# B168B.net
KiCad netlist of a schematic drawn in EAGLE
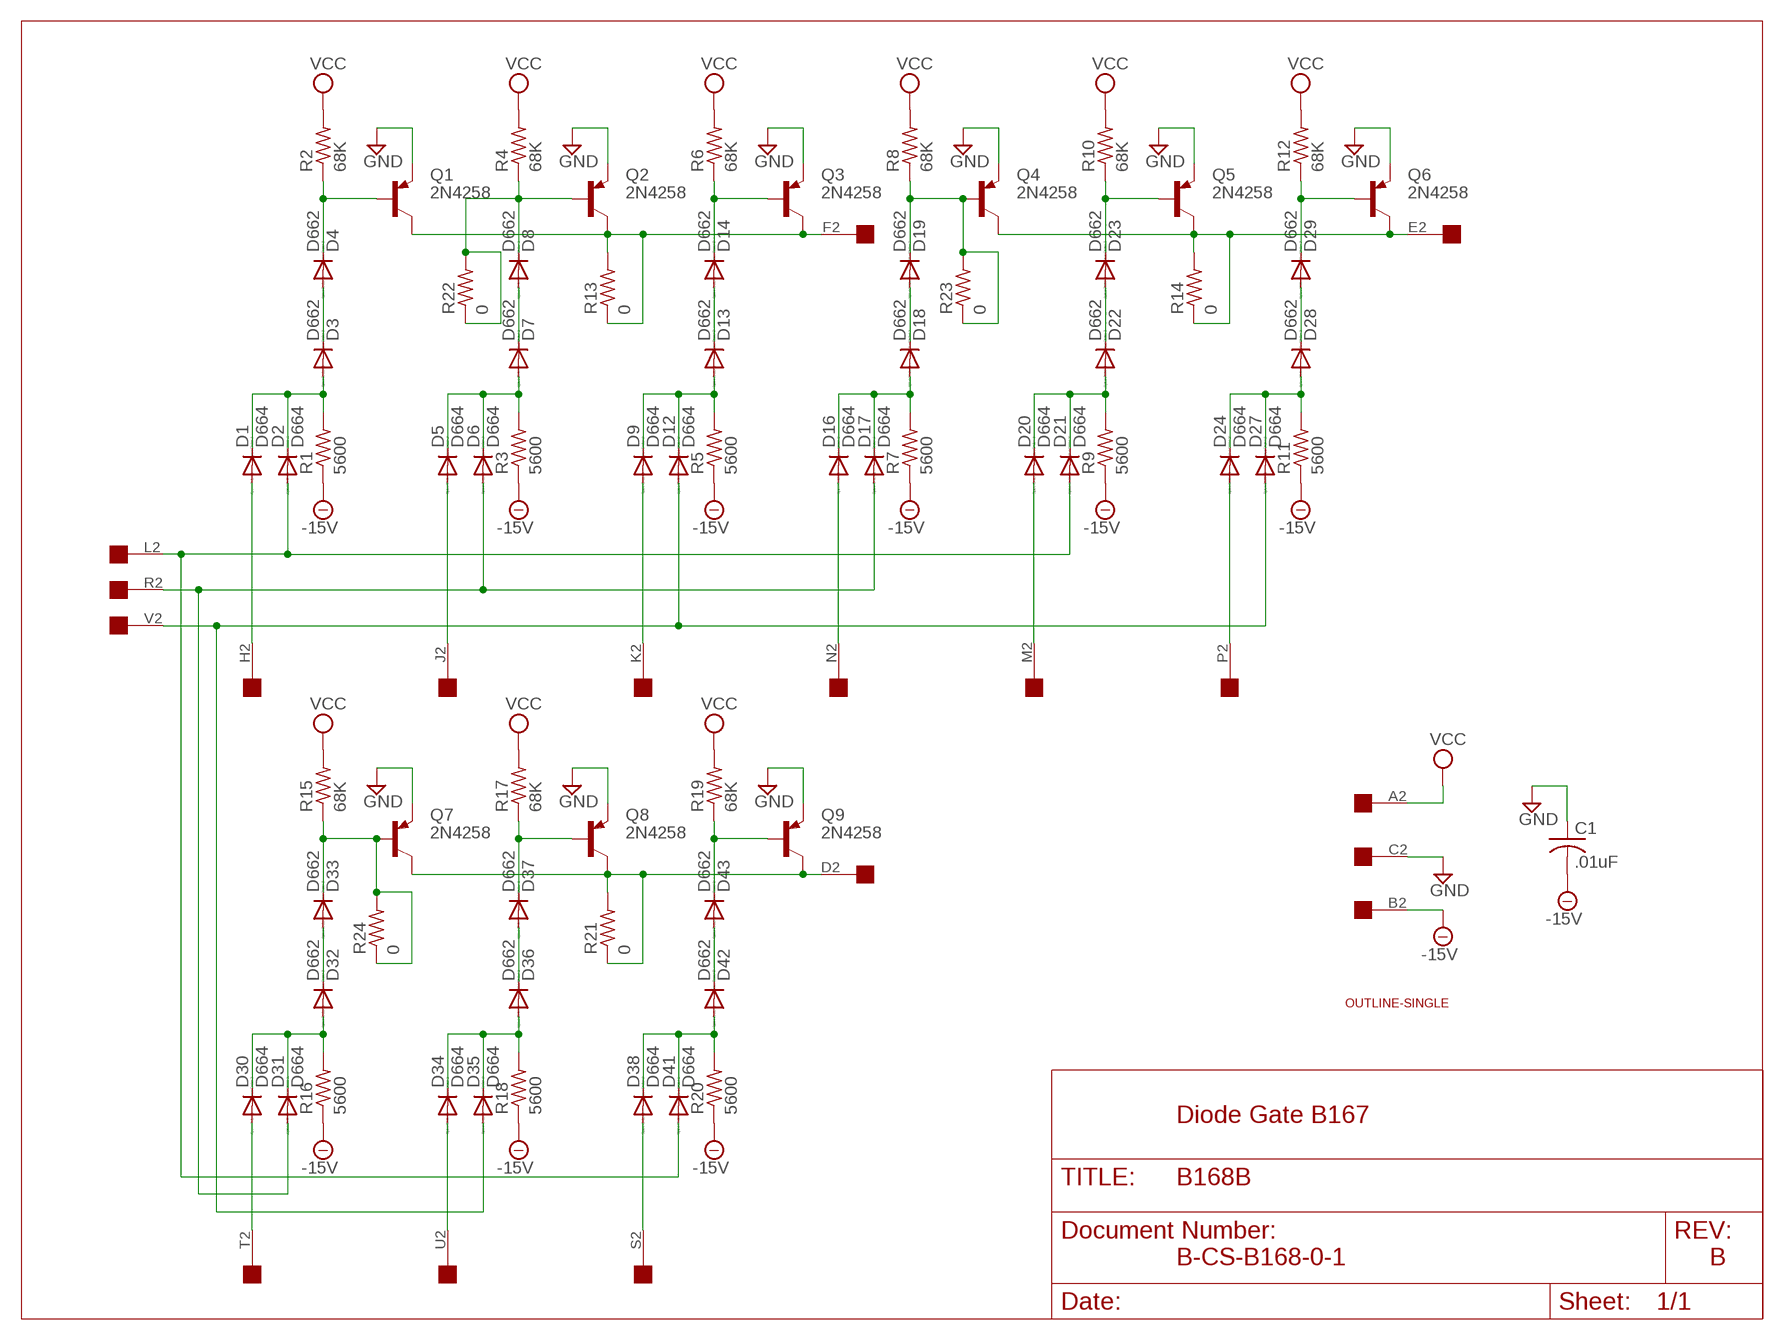
[diagram p0: schematic, sheet 1]

(export (version "E")
  (design (tool "Eeschema 10.0.6"))
  (components
    (comp (ref "C1")
      (value ".01uF")
      (footprint "eagle-import:C063-025X075")
      (libsource (lib "eagle-import") (part "C-US"))
    )
    (comp (ref "D1")
      (value "D664")
      (footprint "eagle-import:DO35-10")
      (libsource (lib "eagle-import") (part "DIODE-DO35-10"))
    )
    (comp (ref "D2")
      (value "D664")
      (footprint "eagle-import:DO35-10")
      (libsource (lib "eagle-import") (part "DIODE-DO35-10"))
    )
    (comp (ref "D3")
      (value "D662")
      (footprint "eagle-import:DO35-10")
      (libsource (lib "eagle-import") (part "DIODE-DO35-10"))
    )
    (comp (ref "D4")
      (value "D662")
      (footprint "eagle-import:DO35-10")
      (libsource (lib "eagle-import") (part "DIODE-DO35-10"))
    )
    (comp (ref "D5")
      (value "D664")
      (footprint "eagle-import:DO35-10")
      (libsource (lib "eagle-import") (part "DIODE-DO35-10"))
    )
    (comp (ref "D6")
      (value "D664")
      (footprint "eagle-import:DO35-10")
      (libsource (lib "eagle-import") (part "DIODE-DO35-10"))
    )
    (comp (ref "D7")
      (value "D662")
      (footprint "eagle-import:DO35-10")
      (libsource (lib "eagle-import") (part "DIODE-DO35-10"))
    )
    (comp (ref "D8")
      (value "D662")
      (footprint "eagle-import:DO35-10")
      (libsource (lib "eagle-import") (part "DIODE-DO35-10"))
    )
    (comp (ref "D9")
      (value "D664")
      (footprint "eagle-import:DO35-10")
      (libsource (lib "eagle-import") (part "DIODE-DO35-10"))
    )
    (comp (ref "D12")
      (value "D664")
      (footprint "eagle-import:DO35-10")
      (libsource (lib "eagle-import") (part "DIODE-DO35-10"))
    )
    (comp (ref "D13")
      (value "D662")
      (footprint "eagle-import:DO35-10")
      (libsource (lib "eagle-import") (part "DIODE-DO35-10"))
    )
    (comp (ref "D14")
      (value "D662")
      (footprint "eagle-import:DO35-10")
      (libsource (lib "eagle-import") (part "DIODE-DO35-10"))
    )
    (comp (ref "D16")
      (value "D664")
      (footprint "eagle-import:DO35-10")
      (libsource (lib "eagle-import") (part "DIODE-DO35-10"))
    )
    (comp (ref "D17")
      (value "D664")
      (footprint "eagle-import:DO35-10")
      (libsource (lib "eagle-import") (part "DIODE-DO35-10"))
    )
    (comp (ref "D18")
      (value "D662")
      (footprint "eagle-import:DO35-10")
      (libsource (lib "eagle-import") (part "DIODE-DO35-10"))
    )
    (comp (ref "D19")
      (value "D662")
      (footprint "eagle-import:DO35-10")
      (libsource (lib "eagle-import") (part "DIODE-DO35-10"))
    )
    (comp (ref "D20")
      (value "D664")
      (footprint "eagle-import:DO35-10")
      (libsource (lib "eagle-import") (part "DIODE-DO35-10"))
    )
    (comp (ref "D21")
      (value "D664")
      (footprint "eagle-import:DO35-10")
      (libsource (lib "eagle-import") (part "DIODE-DO35-10"))
    )
    (comp (ref "D22")
      (value "D662")
      (footprint "eagle-import:DO35-10")
      (libsource (lib "eagle-import") (part "DIODE-DO35-10"))
    )
    (comp (ref "D23")
      (value "D662")
      (footprint "eagle-import:DO35-10")
      (libsource (lib "eagle-import") (part "DIODE-DO35-10"))
    )
    (comp (ref "D24")
      (value "D664")
      (footprint "eagle-import:DO35-10")
      (libsource (lib "eagle-import") (part "DIODE-DO35-10"))
    )
    (comp (ref "D27")
      (value "D664")
      (footprint "eagle-import:DO35-10")
      (libsource (lib "eagle-import") (part "DIODE-DO35-10"))
    )
    (comp (ref "D28")
      (value "D662")
      (footprint "eagle-import:DO35-10")
      (libsource (lib "eagle-import") (part "DIODE-DO35-10"))
    )
    (comp (ref "D29")
      (value "D662")
      (footprint "eagle-import:DO35-10")
      (libsource (lib "eagle-import") (part "DIODE-DO35-10"))
    )
    (comp (ref "D30")
      (value "D664")
      (footprint "eagle-import:DO35-10")
      (libsource (lib "eagle-import") (part "DIODE-DO35-10"))
    )
    (comp (ref "D31")
      (value "D664")
      (footprint "eagle-import:DO35-10")
      (libsource (lib "eagle-import") (part "DIODE-DO35-10"))
    )
    (comp (ref "D32")
      (value "D662")
      (footprint "eagle-import:DO35-10")
      (libsource (lib "eagle-import") (part "DIODE-DO35-10"))
    )
    (comp (ref "D33")
      (value "D662")
      (footprint "eagle-import:DO35-10")
      (libsource (lib "eagle-import") (part "DIODE-DO35-10"))
    )
    (comp (ref "D34")
      (value "D664")
      (footprint "eagle-import:DO35-10")
      (libsource (lib "eagle-import") (part "DIODE-DO35-10"))
    )
    (comp (ref "D35")
      (value "D664")
      (footprint "eagle-import:DO35-10")
      (libsource (lib "eagle-import") (part "DIODE-DO35-10"))
    )
    (comp (ref "D36")
      (value "D662")
      (footprint "eagle-import:DO35-10")
      (libsource (lib "eagle-import") (part "DIODE-DO35-10"))
    )
    (comp (ref "D37")
      (value "D662")
      (footprint "eagle-import:DO35-10")
      (libsource (lib "eagle-import") (part "DIODE-DO35-10"))
    )
    (comp (ref "D38")
      (value "D664")
      (footprint "eagle-import:DO35-10")
      (libsource (lib "eagle-import") (part "DIODE-DO35-10"))
    )
    (comp (ref "D41")
      (value "D664")
      (footprint "eagle-import:DO35-10")
      (libsource (lib "eagle-import") (part "DIODE-DO35-10"))
    )
    (comp (ref "D42")
      (value "D662")
      (footprint "eagle-import:DO35-10")
      (libsource (lib "eagle-import") (part "DIODE-DO35-10"))
    )
    (comp (ref "D43")
      (value "D662")
      (footprint "eagle-import:DO35-10")
      (libsource (lib "eagle-import") (part "DIODE-DO35-10"))
    )
    (comp (ref "Q1")
      (value "2N4258")
      (footprint "eagle-import:TO5")
      (libsource (lib "eagle-import") (part "-PNP-TO5"))
    )
    (comp (ref "Q2")
      (value "2N4258")
      (footprint "eagle-import:TO5")
      (libsource (lib "eagle-import") (part "-PNP-TO5"))
    )
    (comp (ref "Q3")
      (value "2N4258")
      (footprint "eagle-import:TO5")
      (libsource (lib "eagle-import") (part "-PNP-TO5"))
    )
    (comp (ref "Q4")
      (value "2N4258")
      (footprint "eagle-import:TO5")
      (libsource (lib "eagle-import") (part "-PNP-TO5"))
    )
    (comp (ref "Q5")
      (value "2N4258")
      (footprint "eagle-import:TO5")
      (libsource (lib "eagle-import") (part "-PNP-TO5"))
    )
    (comp (ref "Q6")
      (value "2N4258")
      (footprint "eagle-import:TO5")
      (libsource (lib "eagle-import") (part "-PNP-TO5"))
    )
    (comp (ref "Q7")
      (value "2N4258")
      (footprint "eagle-import:TO5")
      (libsource (lib "eagle-import") (part "-PNP-TO5"))
    )
    (comp (ref "Q8")
      (value "2N4258")
      (footprint "eagle-import:TO5")
      (libsource (lib "eagle-import") (part "-PNP-TO5"))
    )
    (comp (ref "Q9")
      (value "2N4258")
      (footprint "eagle-import:TO5")
      (libsource (lib "eagle-import") (part "-PNP-TO5"))
    )
    (comp (ref "R1")
      (value "5600")
      (footprint "eagle-import:0207_10")
      (libsource (lib "eagle-import") (part "R-US_0207/10"))
    )
    (comp (ref "R2")
      (value "68K")
      (footprint "eagle-import:0207_10")
      (libsource (lib "eagle-import") (part "R-US_0207/10"))
    )
    (comp (ref "R3")
      (value "5600")
      (footprint "eagle-import:0207_10")
      (libsource (lib "eagle-import") (part "R-US_0207/10"))
    )
    (comp (ref "R4")
      (value "68K")
      (footprint "eagle-import:0207_10")
      (libsource (lib "eagle-import") (part "R-US_0207/10"))
    )
    (comp (ref "R5")
      (value "5600")
      (footprint "eagle-import:0207_10")
      (libsource (lib "eagle-import") (part "R-US_0207/10"))
    )
    (comp (ref "R6")
      (value "68K")
      (footprint "eagle-import:0207_10")
      (libsource (lib "eagle-import") (part "R-US_0207/10"))
    )
    (comp (ref "R7")
      (value "5600")
      (footprint "eagle-import:0207_10")
      (libsource (lib "eagle-import") (part "R-US_0207/10"))
    )
    (comp (ref "R8")
      (value "68K")
      (footprint "eagle-import:0207_10")
      (libsource (lib "eagle-import") (part "R-US_0207/10"))
    )
    (comp (ref "R9")
      (value "5600")
      (footprint "eagle-import:0207_10")
      (libsource (lib "eagle-import") (part "R-US_0207/10"))
    )
    (comp (ref "R10")
      (value "68K")
      (footprint "eagle-import:0207_10")
      (libsource (lib "eagle-import") (part "R-US_0207/10"))
    )
    (comp (ref "R11")
      (value "5600")
      (footprint "eagle-import:0207_10")
      (libsource (lib "eagle-import") (part "R-US_0207/10"))
    )
    (comp (ref "R12")
      (value "68K")
      (footprint "eagle-import:0207_10")
      (libsource (lib "eagle-import") (part "R-US_0207/10"))
    )
    (comp (ref "R13")
      (value "0")
      (footprint "eagle-import:0207_10")
      (libsource (lib "eagle-import") (part "R-US_0207/10"))
    )
    (comp (ref "R14")
      (value "0")
      (footprint "eagle-import:0207_10")
      (libsource (lib "eagle-import") (part "R-US_0207/10"))
    )
    (comp (ref "R15")
      (value "68K")
      (footprint "eagle-import:0207_10")
      (libsource (lib "eagle-import") (part "R-US_0207/10"))
    )
    (comp (ref "R16")
      (value "5600")
      (footprint "eagle-import:0207_10")
      (libsource (lib "eagle-import") (part "R-US_0207/10"))
    )
    (comp (ref "R17")
      (value "68K")
      (footprint "eagle-import:0207_10")
      (libsource (lib "eagle-import") (part "R-US_0207/10"))
    )
    (comp (ref "R18")
      (value "5600")
      (footprint "eagle-import:0207_10")
      (libsource (lib "eagle-import") (part "R-US_0207/10"))
    )
    (comp (ref "R19")
      (value "68K")
      (footprint "eagle-import:0207_10")
      (libsource (lib "eagle-import") (part "R-US_0207/10"))
    )
    (comp (ref "R20")
      (value "5600")
      (footprint "eagle-import:0207_10")
      (libsource (lib "eagle-import") (part "R-US_0207/10"))
    )
    (comp (ref "R21")
      (value "0")
      (footprint "eagle-import:0207_10")
      (libsource (lib "eagle-import") (part "R-US_0207/10"))
    )
    (comp (ref "R22")
      (value "0")
      (footprint "eagle-import:0207_10")
      (libsource (lib "eagle-import") (part "R-US_0207/10"))
    )
    (comp (ref "R23")
      (value "0")
      (footprint "eagle-import:0207_10")
      (libsource (lib "eagle-import") (part "R-US_0207/10"))
    )
    (comp (ref "R24")
      (value "0")
      (footprint "eagle-import:0207_10")
      (libsource (lib "eagle-import") (part "R-US_0207/10"))
    )
    (comp (ref "U$1")
      (value "OUTLINE-SINGLE")
      (footprint "eagle-import:SINGLE")
      (libsource (lib "eagle-import") (part "OUTLINE-SINGLE"))
    )
    (comp (ref "U$2")
      (value "EDGE-1")
      (footprint "eagle-import:EDGE-CON1")
      (libsource (lib "eagle-import") (part "EDGE-1"))
    )
  )
  (nets
    (net (code "1") (name "-15V") (class "Default")
      (node (ref "C1") (pin "2") (pinfunction "2_2") (pintype "passive"))
      (node (ref "R1") (pin "1") (pinfunction "1_1") (pintype "passive"))
      (node (ref "R11") (pin "1") (pinfunction "1_1") (pintype "passive"))
      (node (ref "R16") (pin "1") (pinfunction "1_1") (pintype "passive"))
      (node (ref "R18") (pin "1") (pinfunction "1_1") (pintype "passive"))
      (node (ref "R20") (pin "1") (pinfunction "1_1") (pintype "passive"))
      (node (ref "R3") (pin "1") (pinfunction "1_1") (pintype "passive"))
      (node (ref "R5") (pin "1") (pinfunction "1_1") (pintype "passive"))
      (node (ref "R7") (pin "1") (pinfunction "1_1") (pintype "passive"))
      (node (ref "R9") (pin "1") (pinfunction "1_1") (pintype "passive"))
      (node (ref "U$2") (pin "B2") (pinfunction "1_B2") (pintype "bidirectional"))
    )
    (net (code "2") (name "GND") (class "Default")
      (node (ref "C1") (pin "1") (pinfunction "1_1") (pintype "passive"))
      (node (ref "Q1") (pin "1") (pinfunction "E_1") (pintype "passive"))
      (node (ref "Q2") (pin "1") (pinfunction "E_1") (pintype "passive"))
      (node (ref "Q3") (pin "1") (pinfunction "E_1") (pintype "passive"))
      (node (ref "Q4") (pin "1") (pinfunction "E_1") (pintype "passive"))
      (node (ref "Q5") (pin "1") (pinfunction "E_1") (pintype "passive"))
      (node (ref "Q6") (pin "1") (pinfunction "E_1") (pintype "passive"))
      (node (ref "Q7") (pin "1") (pinfunction "E_1") (pintype "passive"))
      (node (ref "Q8") (pin "1") (pinfunction "E_1") (pintype "passive"))
      (node (ref "Q9") (pin "1") (pinfunction "E_1") (pintype "passive"))
      (node (ref "U$2") (pin "C2") (pinfunction "1_C2") (pintype "bidirectional"))
    )
    (net (code "3") (name "Net-(D1-PadC)") (class "Default")
      (node (ref "D1") (pin "C") (pinfunction "C_C") (pintype "passive"))
      (node (ref "D2") (pin "C") (pinfunction "C_C") (pintype "passive"))
      (node (ref "D3") (pin "A") (pinfunction "A_A") (pintype "passive"))
      (node (ref "R1") (pin "2") (pinfunction "2_2") (pintype "passive"))
    )
    (net (code "4") (name "Net-(D3-PadC)") (class "Default")
      (node (ref "D3") (pin "C") (pinfunction "C_C") (pintype "passive"))
      (node (ref "D4") (pin "A") (pinfunction "A_A") (pintype "passive"))
    )
    (net (code "5") (name "Net-(D5-PadC)") (class "Default")
      (node (ref "D5") (pin "C") (pinfunction "C_C") (pintype "passive"))
      (node (ref "D6") (pin "C") (pinfunction "C_C") (pintype "passive"))
      (node (ref "D7") (pin "A") (pinfunction "A_A") (pintype "passive"))
      (node (ref "R3") (pin "2") (pinfunction "2_2") (pintype "passive"))
    )
    (net (code "6") (name "Net-(D7-PadC)") (class "Default")
      (node (ref "D7") (pin "C") (pinfunction "C_C") (pintype "passive"))
      (node (ref "D8") (pin "A") (pinfunction "A_A") (pintype "passive"))
    )
    (net (code "7") (name "Net-(D12-PadC)") (class "Default")
      (node (ref "D12") (pin "C") (pinfunction "C_C") (pintype "passive"))
      (node (ref "D13") (pin "A") (pinfunction "A_A") (pintype "passive"))
      (node (ref "D9") (pin "C") (pinfunction "C_C") (pintype "passive"))
      (node (ref "R5") (pin "2") (pinfunction "2_2") (pintype "passive"))
    )
    (net (code "8") (name "Net-(D13-PadC)") (class "Default")
      (node (ref "D13") (pin "C") (pinfunction "C_C") (pintype "passive"))
      (node (ref "D14") (pin "A") (pinfunction "A_A") (pintype "passive"))
    )
    (net (code "9") (name "Net-(D16-PadC)") (class "Default")
      (node (ref "D16") (pin "C") (pinfunction "C_C") (pintype "passive"))
      (node (ref "D17") (pin "C") (pinfunction "C_C") (pintype "passive"))
      (node (ref "D18") (pin "A") (pinfunction "A_A") (pintype "passive"))
      (node (ref "R7") (pin "2") (pinfunction "2_2") (pintype "passive"))
    )
    (net (code "10") (name "Net-(D18-PadC)") (class "Default")
      (node (ref "D18") (pin "C") (pinfunction "C_C") (pintype "passive"))
      (node (ref "D19") (pin "A") (pinfunction "A_A") (pintype "passive"))
    )
    (net (code "11") (name "Net-(D20-PadC)") (class "Default")
      (node (ref "D20") (pin "C") (pinfunction "C_C") (pintype "passive"))
      (node (ref "D21") (pin "C") (pinfunction "C_C") (pintype "passive"))
      (node (ref "D22") (pin "A") (pinfunction "A_A") (pintype "passive"))
      (node (ref "R9") (pin "2") (pinfunction "2_2") (pintype "passive"))
    )
    (net (code "12") (name "Net-(D22-PadC)") (class "Default")
      (node (ref "D22") (pin "C") (pinfunction "C_C") (pintype "passive"))
      (node (ref "D23") (pin "A") (pinfunction "A_A") (pintype "passive"))
    )
    (net (code "13") (name "Net-(D24-PadC)") (class "Default")
      (node (ref "D24") (pin "C") (pinfunction "C_C") (pintype "passive"))
      (node (ref "D27") (pin "C") (pinfunction "C_C") (pintype "passive"))
      (node (ref "D28") (pin "A") (pinfunction "A_A") (pintype "passive"))
      (node (ref "R11") (pin "2") (pinfunction "2_2") (pintype "passive"))
    )
    (net (code "14") (name "Net-(D28-PadC)") (class "Default")
      (node (ref "D28") (pin "C") (pinfunction "C_C") (pintype "passive"))
      (node (ref "D29") (pin "A") (pinfunction "A_A") (pintype "passive"))
    )
    (net (code "15") (name "Net-(D30-PadC)") (class "Default")
      (node (ref "D30") (pin "C") (pinfunction "C_C") (pintype "passive"))
      (node (ref "D31") (pin "C") (pinfunction "C_C") (pintype "passive"))
      (node (ref "D32") (pin "A") (pinfunction "A_A") (pintype "passive"))
      (node (ref "R16") (pin "2") (pinfunction "2_2") (pintype "passive"))
    )
    (net (code "16") (name "Net-(D32-PadC)") (class "Default")
      (node (ref "D32") (pin "C") (pinfunction "C_C") (pintype "passive"))
      (node (ref "D33") (pin "A") (pinfunction "A_A") (pintype "passive"))
    )
    (net (code "17") (name "Net-(D34-PadC)") (class "Default")
      (node (ref "D34") (pin "C") (pinfunction "C_C") (pintype "passive"))
      (node (ref "D35") (pin "C") (pinfunction "C_C") (pintype "passive"))
      (node (ref "D36") (pin "A") (pinfunction "A_A") (pintype "passive"))
      (node (ref "R18") (pin "2") (pinfunction "2_2") (pintype "passive"))
    )
    (net (code "18") (name "Net-(D36-PadC)") (class "Default")
      (node (ref "D36") (pin "C") (pinfunction "C_C") (pintype "passive"))
      (node (ref "D37") (pin "A") (pinfunction "A_A") (pintype "passive"))
    )
    (net (code "19") (name "Net-(D38-PadC)") (class "Default")
      (node (ref "D38") (pin "C") (pinfunction "C_C") (pintype "passive"))
      (node (ref "D41") (pin "C") (pinfunction "C_C") (pintype "passive"))
      (node (ref "D42") (pin "A") (pinfunction "A_A") (pintype "passive"))
      (node (ref "R20") (pin "2") (pinfunction "2_2") (pintype "passive"))
    )
    (net (code "20") (name "Net-(D42-PadC)") (class "Default")
      (node (ref "D42") (pin "C") (pinfunction "C_C") (pintype "passive"))
      (node (ref "D43") (pin "A") (pinfunction "A_A") (pintype "passive"))
    )
    (net (code "21") (name "Net-(Q1-B)") (class "Default")
      (node (ref "D4") (pin "C") (pinfunction "C_C") (pintype "passive"))
      (node (ref "Q1") (pin "2") (pinfunction "B_2") (pintype "passive"))
      (node (ref "R2") (pin "1") (pinfunction "1_1") (pintype "passive"))
    )
    (net (code "22") (name "Net-(Q1-C)") (class "Default")
      (node (ref "Q1") (pin "3") (pinfunction "C_3") (pintype "passive"))
      (node (ref "Q2") (pin "3") (pinfunction "C_3") (pintype "passive"))
      (node (ref "Q3") (pin "3") (pinfunction "C_3") (pintype "passive"))
      (node (ref "R13") (pin "1") (pinfunction "1_1") (pintype "passive"))
      (node (ref "R13") (pin "2") (pinfunction "2_2") (pintype "passive"))
      (node (ref "U$2") (pin "F2") (pinfunction "1_F2") (pintype "bidirectional"))
    )
    (net (code "23") (name "Net-(Q2-B)") (class "Default")
      (node (ref "D8") (pin "C") (pinfunction "C_C") (pintype "passive"))
      (node (ref "Q2") (pin "2") (pinfunction "B_2") (pintype "passive"))
      (node (ref "R22") (pin "1") (pinfunction "1_1") (pintype "passive"))
      (node (ref "R22") (pin "2") (pinfunction "2_2") (pintype "passive"))
      (node (ref "R4") (pin "1") (pinfunction "1_1") (pintype "passive"))
    )
    (net (code "24") (name "Net-(Q3-B)") (class "Default")
      (node (ref "D14") (pin "C") (pinfunction "C_C") (pintype "passive"))
      (node (ref "Q3") (pin "2") (pinfunction "B_2") (pintype "passive"))
      (node (ref "R6") (pin "1") (pinfunction "1_1") (pintype "passive"))
    )
    (net (code "25") (name "Net-(Q4-B)") (class "Default")
      (node (ref "D19") (pin "C") (pinfunction "C_C") (pintype "passive"))
      (node (ref "Q4") (pin "2") (pinfunction "B_2") (pintype "passive"))
      (node (ref "R23") (pin "1") (pinfunction "1_1") (pintype "passive"))
      (node (ref "R23") (pin "2") (pinfunction "2_2") (pintype "passive"))
      (node (ref "R8") (pin "1") (pinfunction "1_1") (pintype "passive"))
    )
    (net (code "26") (name "Net-(Q4-C)") (class "Default")
      (node (ref "Q4") (pin "3") (pinfunction "C_3") (pintype "passive"))
      (node (ref "Q5") (pin "3") (pinfunction "C_3") (pintype "passive"))
      (node (ref "Q6") (pin "3") (pinfunction "C_3") (pintype "passive"))
      (node (ref "R14") (pin "1") (pinfunction "1_1") (pintype "passive"))
      (node (ref "R14") (pin "2") (pinfunction "2_2") (pintype "passive"))
      (node (ref "U$2") (pin "E2") (pinfunction "1_E2") (pintype "bidirectional"))
    )
    (net (code "27") (name "Net-(Q5-B)") (class "Default")
      (node (ref "D23") (pin "C") (pinfunction "C_C") (pintype "passive"))
      (node (ref "Q5") (pin "2") (pinfunction "B_2") (pintype "passive"))
      (node (ref "R10") (pin "1") (pinfunction "1_1") (pintype "passive"))
    )
    (net (code "28") (name "Net-(Q6-B)") (class "Default")
      (node (ref "D29") (pin "C") (pinfunction "C_C") (pintype "passive"))
      (node (ref "Q6") (pin "2") (pinfunction "B_2") (pintype "passive"))
      (node (ref "R12") (pin "1") (pinfunction "1_1") (pintype "passive"))
    )
    (net (code "29") (name "Net-(Q7-B)") (class "Default")
      (node (ref "D33") (pin "C") (pinfunction "C_C") (pintype "passive"))
      (node (ref "Q7") (pin "2") (pinfunction "B_2") (pintype "passive"))
      (node (ref "R15") (pin "1") (pinfunction "1_1") (pintype "passive"))
      (node (ref "R24") (pin "1") (pinfunction "1_1") (pintype "passive"))
      (node (ref "R24") (pin "2") (pinfunction "2_2") (pintype "passive"))
    )
    (net (code "30") (name "Net-(Q7-C)") (class "Default")
      (node (ref "Q7") (pin "3") (pinfunction "C_3") (pintype "passive"))
      (node (ref "Q8") (pin "3") (pinfunction "C_3") (pintype "passive"))
      (node (ref "Q9") (pin "3") (pinfunction "C_3") (pintype "passive"))
      (node (ref "R21") (pin "1") (pinfunction "1_1") (pintype "passive"))
      (node (ref "R21") (pin "2") (pinfunction "2_2") (pintype "passive"))
      (node (ref "U$2") (pin "D2") (pinfunction "1_D2") (pintype "bidirectional"))
    )
    (net (code "31") (name "Net-(Q8-B)") (class "Default")
      (node (ref "D37") (pin "C") (pinfunction "C_C") (pintype "passive"))
      (node (ref "Q8") (pin "2") (pinfunction "B_2") (pintype "passive"))
      (node (ref "R17") (pin "1") (pinfunction "1_1") (pintype "passive"))
    )
    (net (code "32") (name "Net-(Q9-B)") (class "Default")
      (node (ref "D43") (pin "C") (pinfunction "C_C") (pintype "passive"))
      (node (ref "Q9") (pin "2") (pinfunction "B_2") (pintype "passive"))
      (node (ref "R19") (pin "1") (pinfunction "1_1") (pintype "passive"))
    )
    (net (code "33") (name "Net-(U$2G-1)") (class "Default")
      (node (ref "D1") (pin "A") (pinfunction "A_A") (pintype "passive"))
      (node (ref "U$2") (pin "H2") (pinfunction "1_H2") (pintype "bidirectional"))
    )
    (net (code "34") (name "Net-(U$2H-1)") (class "Default")
      (node (ref "D5") (pin "A") (pinfunction "A_A") (pintype "passive"))
      (node (ref "U$2") (pin "J2") (pinfunction "1_J2") (pintype "bidirectional"))
    )
    (net (code "35") (name "Net-(U$2I-1)") (class "Default")
      (node (ref "D9") (pin "A") (pinfunction "A_A") (pintype "passive"))
      (node (ref "U$2") (pin "K2") (pinfunction "1_K2") (pintype "bidirectional"))
    )
    (net (code "36") (name "Net-(U$2J-1)") (class "Default")
      (node (ref "D2") (pin "A") (pinfunction "A_A") (pintype "passive"))
      (node (ref "D21") (pin "A") (pinfunction "A_A") (pintype "passive"))
      (node (ref "D41") (pin "A") (pinfunction "A_A") (pintype "passive"))
      (node (ref "U$2") (pin "L2") (pinfunction "1_L2") (pintype "bidirectional"))
    )
    (net (code "37") (name "Net-(U$2K-1)") (class "Default")
      (node (ref "D20") (pin "A") (pinfunction "A_A") (pintype "passive"))
      (node (ref "U$2") (pin "M2") (pinfunction "1_M2") (pintype "bidirectional"))
    )
    (net (code "38") (name "Net-(U$2L-1)") (class "Default")
      (node (ref "D16") (pin "A") (pinfunction "A_A") (pintype "passive"))
      (node (ref "U$2") (pin "N2") (pinfunction "1_N2") (pintype "bidirectional"))
    )
    (net (code "39") (name "Net-(U$2M-1)") (class "Default")
      (node (ref "D24") (pin "A") (pinfunction "A_A") (pintype "passive"))
      (node (ref "U$2") (pin "P2") (pinfunction "1_P2") (pintype "bidirectional"))
    )
    (net (code "40") (name "Net-(U$2N-1)") (class "Default")
      (node (ref "D17") (pin "A") (pinfunction "A_A") (pintype "passive"))
      (node (ref "D31") (pin "A") (pinfunction "A_A") (pintype "passive"))
      (node (ref "D6") (pin "A") (pinfunction "A_A") (pintype "passive"))
      (node (ref "U$2") (pin "R2") (pinfunction "1_R2") (pintype "bidirectional"))
    )
    (net (code "41") (name "Net-(U$2O-1)") (class "Default")
      (node (ref "D38") (pin "A") (pinfunction "A_A") (pintype "passive"))
      (node (ref "U$2") (pin "S2") (pinfunction "1_S2") (pintype "bidirectional"))
    )
    (net (code "42") (name "Net-(U$2P-1)") (class "Default")
      (node (ref "D30") (pin "A") (pinfunction "A_A") (pintype "passive"))
      (node (ref "U$2") (pin "T2") (pinfunction "1_T2") (pintype "bidirectional"))
    )
    (net (code "43") (name "Net-(U$2Q-1)") (class "Default")
      (node (ref "D34") (pin "A") (pinfunction "A_A") (pintype "passive"))
      (node (ref "U$2") (pin "U2") (pinfunction "1_U2") (pintype "bidirectional"))
    )
    (net (code "44") (name "Net-(U$2R-1)") (class "Default")
      (node (ref "D12") (pin "A") (pinfunction "A_A") (pintype "passive"))
      (node (ref "D27") (pin "A") (pinfunction "A_A") (pintype "passive"))
      (node (ref "D35") (pin "A") (pinfunction "A_A") (pintype "passive"))
      (node (ref "U$2") (pin "V2") (pinfunction "1_V2") (pintype "bidirectional"))
    )
    (net (code "45") (name "VCC") (class "Default")
      (node (ref "R10") (pin "2") (pinfunction "2_2") (pintype "passive"))
      (node (ref "R12") (pin "2") (pinfunction "2_2") (pintype "passive"))
      (node (ref "R15") (pin "2") (pinfunction "2_2") (pintype "passive"))
      (node (ref "R17") (pin "2") (pinfunction "2_2") (pintype "passive"))
      (node (ref "R19") (pin "2") (pinfunction "2_2") (pintype "passive"))
      (node (ref "R2") (pin "2") (pinfunction "2_2") (pintype "passive"))
      (node (ref "R4") (pin "2") (pinfunction "2_2") (pintype "passive"))
      (node (ref "R6") (pin "2") (pinfunction "2_2") (pintype "passive"))
      (node (ref "R8") (pin "2") (pinfunction "2_2") (pintype "passive"))
      (node (ref "U$2") (pin "A2") (pinfunction "1_A2") (pintype "bidirectional"))
    )
  )
)
